# OVER_HEATING_DETECTION.net
KiCad netlist of a schematic drawn in EAGLE
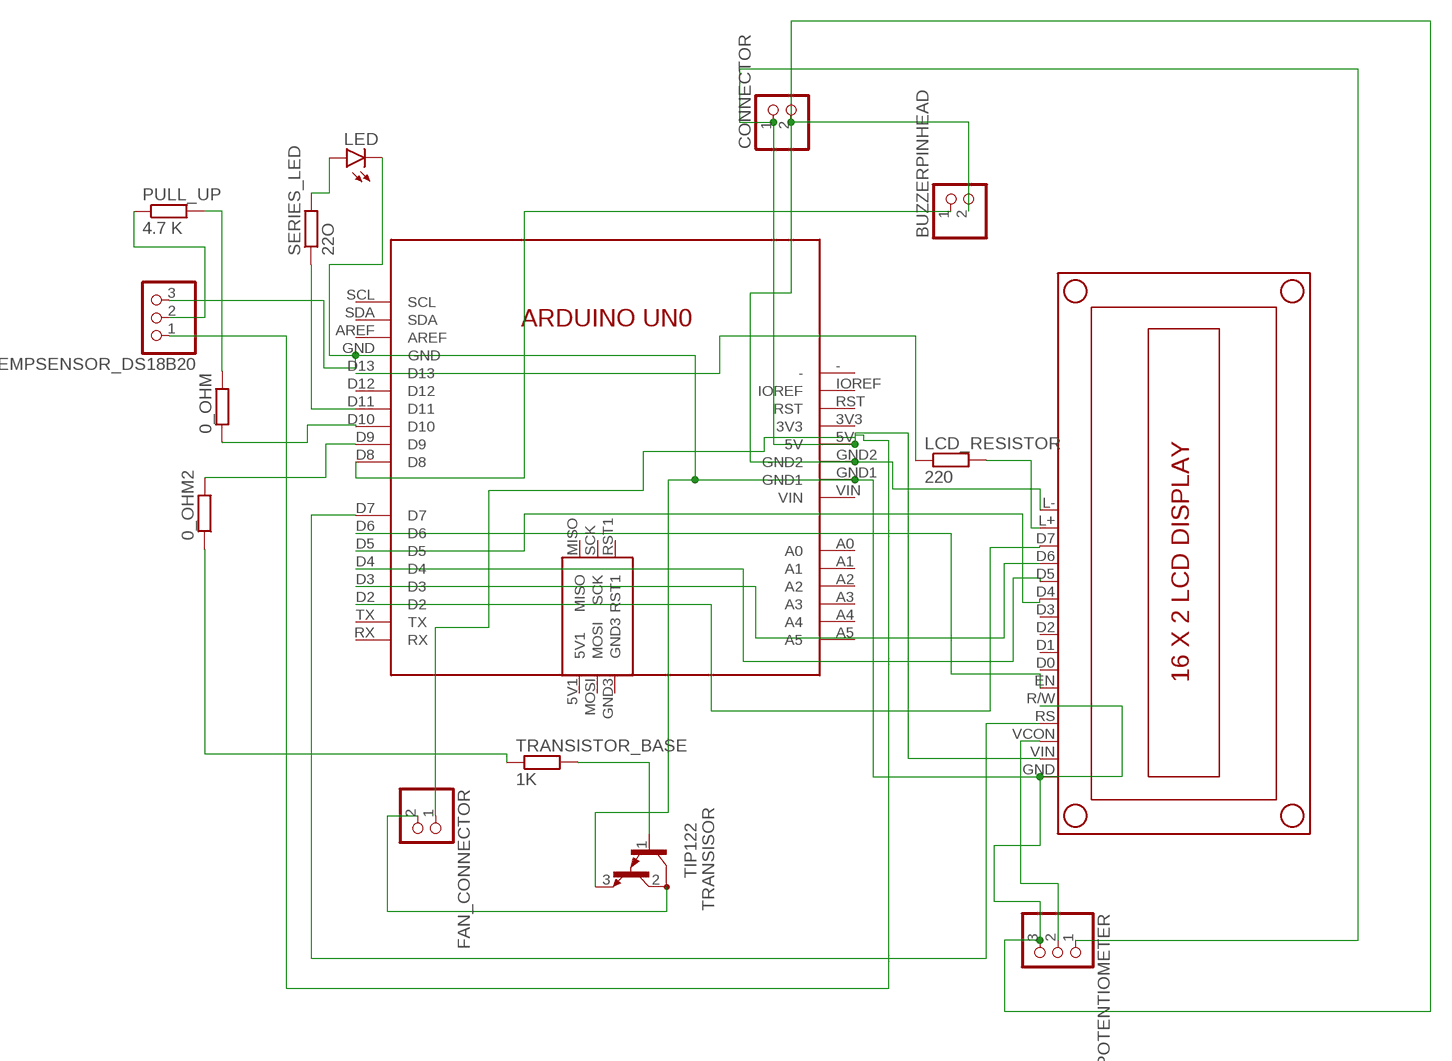
[diagram p0: schematic, sheet 1]

(export (version "E")
  (design (tool "Eeschema 10.0.6"))
  (components
    (comp (ref "0_OHM")
      (value "R-EU_0204/7")
      (footprint "eagle-import:0204_7")
      (libsource (lib "eagle-import") (part "R-EU_0204/7"))
    )
    (comp (ref "0_OHM2")
      (value "R-EU_0204/7")
      (footprint "eagle-import:0204_7")
      (libsource (lib "eagle-import") (part "R-EU_0204/7"))
    )
    (comp (ref "BUZZERPINHEAD")
      (value "PINHD-1X2")
      (footprint "eagle-import:1X02")
      (libsource (lib "eagle-import") (part "PINHD-1X2"))
    )
    (comp (ref "CONNECTOR")
      (value "PINHD-1X2")
      (footprint "eagle-import:1X02")
      (libsource (lib "eagle-import") (part "PINHD-1X2"))
    )
    (comp (ref "FAN_CONNECTOR")
      (value "PINHD-1X2")
      (footprint "eagle-import:1X02")
      (libsource (lib "eagle-import") (part "PINHD-1X2"))
    )
    (comp (ref "LCD_RESISTOR")
      (value "220")
      (footprint "eagle-import:0204_7")
      (libsource (lib "eagle-import") (part "R-EU_0204/7"))
    )
    (comp (ref "LED")
      (value "LED5MM")
      (footprint "eagle-import:LED5MM")
      (libsource (lib "eagle-import") (part "LED5MM"))
    )
    (comp (ref "POTENTIOMETER")
      (value "PINHD-1X3")
      (footprint "eagle-import:1X03")
      (libsource (lib "eagle-import") (part "PINHD-1X3"))
    )
    (comp (ref "PULL_UP")
      (value "4.7 K")
      (footprint "eagle-import:0204_7")
      (libsource (lib "eagle-import") (part "R-EU_0204/7"))
    )
    (comp (ref "SERIES_LED")
      (value "22O")
      (footprint "eagle-import:0204_7")
      (libsource (lib "eagle-import") (part "R-EU_0204/7"))
    )
    (comp (ref "TEMPSENSOR_DS18B20")
      (value "PINHD-1X3")
      (footprint "eagle-import:1X03")
      (libsource (lib "eagle-import") (part "PINHD-1X3"))
    )
    (comp (ref "TRANSISOR")
      (value "TIP122")
      (footprint "eagle-import:TO220")
      (libsource (lib "eagle-import") (part "TIP122"))
    )
    (comp (ref "TRANSISTOR_BASE")
      (value "1K")
      (footprint "eagle-import:0204_7")
      (libsource (lib "eagle-import") (part "R-EU_0204/7"))
    )
    (comp (ref "U$1")
      (value "ARDUINO_UNO")
      (footprint "eagle-import:ARDUINO_UNO")
      (libsource (lib "eagle-import") (part "ARDUINO_UNO"))
    )
    (comp (ref "U$2")
      (value "16X2_LCD_DISPLAY")
      (footprint "eagle-import:16X2_LCD_DISPLAY")
      (libsource (lib "eagle-import") (part "16X2_LCD_DISPLAY"))
    )
  )
  (nets
    (net (code "1") (name "Net-(0_OHM-Pad1)") (class "Default")
      (node (ref "0_OHM") (pin "1") (pinfunction "1_1") (pintype "passive"))
      (node (ref "U$1") (pin "D10") (pinfunction "D10_D10") (pintype "bidirectional"))
    )
    (net (code "2") (name "Net-(0_OHM-Pad2)") (class "Default")
      (node (ref "0_OHM") (pin "2") (pinfunction "2_2") (pintype "passive"))
      (node (ref "PULL_UP") (pin "2") (pinfunction "2_2") (pintype "passive"))
    )
    (net (code "3") (name "Net-(0_OHM2-Pad1)") (class "Default")
      (node (ref "0_OHM2") (pin "1") (pinfunction "1_1") (pintype "passive"))
      (node (ref "TRANSISTOR_BASE") (pin "1") (pinfunction "1_1") (pintype "passive"))
    )
    (net (code "4") (name "Net-(0_OHM2-Pad2)") (class "Default")
      (node (ref "0_OHM2") (pin "2") (pinfunction "2_2") (pintype "passive"))
      (node (ref "U$1") (pin "D9") (pinfunction "D9_D9") (pintype "bidirectional"))
    )
    (net (code "5") (name "Net-(BUZZERPINHEAD-Pad1)") (class "Default")
      (node (ref "BUZZERPINHEAD") (pin "1") (pinfunction "1_1") (pintype "passive"))
      (node (ref "U$1") (pin "D8") (pinfunction "D8_D8") (pintype "bidirectional"))
    )
    (net (code "6") (name "Net-(CONNECTOR-Pad1)") (class "Default")
      (node (ref "CONNECTOR") (pin "1") (pinfunction "1_1") (pintype "passive"))
      (node (ref "FAN_CONNECTOR") (pin "1") (pinfunction "1_1") (pintype "passive"))
      (node (ref "POTENTIOMETER") (pin "1") (pinfunction "1_1") (pintype "passive"))
      (node (ref "TEMPSENSOR_DS18B20") (pin "1") (pinfunction "1_1") (pintype "passive"))
      (node (ref "U$1") (pin "5V") (pinfunction "5V_5V") (pintype "bidirectional"))
      (node (ref "U$2") (pin "VIN") (pinfunction "VIN_VIN") (pintype "bidirectional"))
    )
    (net (code "7") (name "Net-(LCD_RESISTOR-Pad1)") (class "Default")
      (node (ref "LCD_RESISTOR") (pin "1") (pinfunction "1_1") (pintype "passive"))
      (node (ref "U$1") (pin "D13") (pinfunction "D13_D13") (pintype "bidirectional"))
    )
    (net (code "8") (name "Net-(LCD_RESISTOR-Pad2)") (class "Default")
      (node (ref "LCD_RESISTOR") (pin "2") (pinfunction "2_2") (pintype "passive"))
      (node (ref "U$2") (pin "L+") (pinfunction "L+_L+") (pintype "bidirectional"))
    )
    (net (code "9") (name "Net-(LED-C)") (class "Default")
      (node (ref "BUZZERPINHEAD") (pin "2") (pinfunction "2_2") (pintype "passive"))
      (node (ref "CONNECTOR") (pin "2") (pinfunction "2_2") (pintype "passive"))
      (node (ref "LED") (pin "K") (pinfunction "C_K") (pintype "passive"))
      (node (ref "POTENTIOMETER") (pin "3") (pinfunction "3_3") (pintype "passive"))
      (node (ref "TEMPSENSOR_DS18B20") (pin "3") (pinfunction "3_3") (pintype "passive"))
      (node (ref "TRANSISOR") (pin "3") (pinfunction "E_3") (pintype "passive"))
      (node (ref "U$1") (pin "GND") (pinfunction "GND_GND") (pintype "bidirectional"))
      (node (ref "U$1") (pin "GND1") (pinfunction "GND1_GND1") (pintype "bidirectional"))
      (node (ref "U$1") (pin "GND2") (pinfunction "GND2_GND2") (pintype "bidirectional"))
      (node (ref "U$2") (pin "GND") (pinfunction "GND_GND") (pintype "bidirectional"))
      (node (ref "U$2") (pin "L-") (pinfunction "L-_L-") (pintype "bidirectional"))
      (node (ref "U$2") (pin "R/W") (pinfunction "R/W_R/W") (pintype "bidirectional"))
    )
    (net (code "10") (name "Net-(LED-PadA)") (class "Default")
      (node (ref "LED") (pin "A") (pinfunction "A_A") (pintype "passive"))
      (node (ref "SERIES_LED") (pin "2") (pinfunction "2_2") (pintype "passive"))
    )
    (net (code "11") (name "Net-(POTENTIOMETER-Pad2)") (class "Default")
      (node (ref "POTENTIOMETER") (pin "2") (pinfunction "2_2") (pintype "passive"))
      (node (ref "U$2") (pin "VCON") (pinfunction "VCON_VCON") (pintype "bidirectional"))
    )
    (net (code "12") (name "Net-(PULL_UP-Pad1)") (class "Default")
      (node (ref "PULL_UP") (pin "1") (pinfunction "1_1") (pintype "passive"))
      (node (ref "TEMPSENSOR_DS18B20") (pin "2") (pinfunction "2_2") (pintype "passive"))
    )
    (net (code "13") (name "Net-(SERIES_LED-Pad1)") (class "Default")
      (node (ref "SERIES_LED") (pin "1") (pinfunction "1_1") (pintype "passive"))
      (node (ref "U$1") (pin "D11") (pinfunction "D11_D11") (pintype "bidirectional"))
    )
    (net (code "14") (name "Net-(TRANSISOR-B)") (class "Default")
      (node (ref "TRANSISOR") (pin "1") (pinfunction "B_1") (pintype "passive"))
      (node (ref "TRANSISTOR_BASE") (pin "2") (pinfunction "2_2") (pintype "passive"))
    )
    (net (code "15") (name "Net-(TRANSISOR-C)") (class "Default")
      (node (ref "FAN_CONNECTOR") (pin "2") (pinfunction "2_2") (pintype "passive"))
      (node (ref "TRANSISOR") (pin "2") (pinfunction "C_2") (pintype "passive"))
    )
    (net (code "16") (name "Net-(U$1-PadD2)") (class "Default")
      (node (ref "U$1") (pin "D2") (pinfunction "D2_D2") (pintype "bidirectional"))
      (node (ref "U$2") (pin "D7") (pinfunction "D7_D7") (pintype "bidirectional"))
    )
    (net (code "17") (name "Net-(U$1-PadD3)") (class "Default")
      (node (ref "U$1") (pin "D3") (pinfunction "D3_D3") (pintype "bidirectional"))
      (node (ref "U$2") (pin "D6") (pinfunction "D6_D6") (pintype "bidirectional"))
    )
    (net (code "18") (name "Net-(U$1-PadD4)") (class "Default")
      (node (ref "U$1") (pin "D4") (pinfunction "D4_D4") (pintype "bidirectional"))
      (node (ref "U$2") (pin "D5") (pinfunction "D5_D5") (pintype "bidirectional"))
    )
    (net (code "19") (name "Net-(U$1-PadD5)") (class "Default")
      (node (ref "U$1") (pin "D5") (pinfunction "D5_D5") (pintype "bidirectional"))
      (node (ref "U$2") (pin "D4") (pinfunction "D4_D4") (pintype "bidirectional"))
    )
    (net (code "20") (name "Net-(U$1-PadD6)") (class "Default")
      (node (ref "U$1") (pin "D6") (pinfunction "D6_D6") (pintype "bidirectional"))
      (node (ref "U$2") (pin "EN") (pinfunction "EN_EN") (pintype "bidirectional"))
    )
    (net (code "21") (name "Net-(U$1-PadD7)") (class "Default")
      (node (ref "U$1") (pin "D7") (pinfunction "D7_D7") (pintype "bidirectional"))
      (node (ref "U$2") (pin "RS") (pinfunction "RS_RS") (pintype "bidirectional"))
    )
    (net (code "22") (name "unconnected-(U$1-Pad-)") (class "Default")
      (node (ref "U$1") (pin "-") (pinfunction "-_-") (pintype "bidirectional"))
    )
    (net (code "23") (name "unconnected-(U$1-Pad3V3)") (class "Default")
      (node (ref "U$1") (pin "3V3") (pinfunction "3V3_3V3") (pintype "bidirectional"))
    )
    (net (code "24") (name "unconnected-(U$1-Pad5V1)") (class "Default")
      (node (ref "U$1") (pin "5V1") (pinfunction "5V1_5V1") (pintype "bidirectional"))
    )
    (net (code "25") (name "unconnected-(U$1-PadA0)") (class "Default")
      (node (ref "U$1") (pin "A0") (pinfunction "A0_A0") (pintype "bidirectional"))
    )
    (net (code "26") (name "unconnected-(U$1-PadA1)") (class "Default")
      (node (ref "U$1") (pin "A1") (pinfunction "A1_A1") (pintype "bidirectional"))
    )
    (net (code "27") (name "unconnected-(U$1-PadA2)") (class "Default")
      (node (ref "U$1") (pin "A2") (pinfunction "A2_A2") (pintype "bidirectional"))
    )
    (net (code "28") (name "unconnected-(U$1-PadA3)") (class "Default")
      (node (ref "U$1") (pin "A3") (pinfunction "A3_A3") (pintype "bidirectional"))
    )
    (net (code "29") (name "unconnected-(U$1-PadA4)") (class "Default")
      (node (ref "U$1") (pin "A4") (pinfunction "A4_A4") (pintype "bidirectional"))
    )
    (net (code "30") (name "unconnected-(U$1-PadA5)") (class "Default")
      (node (ref "U$1") (pin "A5") (pinfunction "A5_A5") (pintype "bidirectional"))
    )
    (net (code "31") (name "unconnected-(U$1-PadAREF)") (class "Default")
      (node (ref "U$1") (pin "AREF") (pinfunction "AREF_AREF") (pintype "bidirectional"))
    )
    (net (code "32") (name "unconnected-(U$1-PadD12)") (class "Default")
      (node (ref "U$1") (pin "D12") (pinfunction "D12_D12") (pintype "bidirectional"))
    )
    (net (code "33") (name "unconnected-(U$1-PadGND3)") (class "Default")
      (node (ref "U$1") (pin "GND3") (pinfunction "GND3_GND3") (pintype "bidirectional"))
    )
    (net (code "34") (name "unconnected-(U$1-PadIOREF)") (class "Default")
      (node (ref "U$1") (pin "IOREF") (pinfunction "IOREF_IOREF") (pintype "bidirectional"))
    )
    (net (code "35") (name "unconnected-(U$1-PadMISO)") (class "Default")
      (node (ref "U$1") (pin "MISO") (pinfunction "MISO_MISO") (pintype "bidirectional"))
    )
    (net (code "36") (name "unconnected-(U$1-PadMOSI)") (class "Default")
      (node (ref "U$1") (pin "MOSI") (pinfunction "MOSI_MOSI") (pintype "bidirectional"))
    )
    (net (code "37") (name "unconnected-(U$1-PadRST)") (class "Default")
      (node (ref "U$1") (pin "RST") (pinfunction "RST_RST") (pintype "bidirectional"))
    )
    (net (code "38") (name "unconnected-(U$1-PadRST1)") (class "Default")
      (node (ref "U$1") (pin "RST1") (pinfunction "RST1_RST1") (pintype "bidirectional"))
    )
    (net (code "39") (name "unconnected-(U$1-PadRX)") (class "Default")
      (node (ref "U$1") (pin "RX") (pinfunction "RX_RX") (pintype "bidirectional"))
    )
    (net (code "40") (name "unconnected-(U$1-PadSCK)") (class "Default")
      (node (ref "U$1") (pin "SCK") (pinfunction "SCK_SCK") (pintype "bidirectional"))
    )
    (net (code "41") (name "unconnected-(U$1-PadSCL)") (class "Default")
      (node (ref "U$1") (pin "SCL") (pinfunction "SCL_SCL") (pintype "bidirectional"))
    )
    (net (code "42") (name "unconnected-(U$1-PadSDA)") (class "Default")
      (node (ref "U$1") (pin "SDA") (pinfunction "SDA_SDA") (pintype "bidirectional"))
    )
    (net (code "43") (name "unconnected-(U$1-PadTX)") (class "Default")
      (node (ref "U$1") (pin "TX") (pinfunction "TX_TX") (pintype "bidirectional"))
    )
    (net (code "44") (name "unconnected-(U$1-PadVIN)") (class "Default")
      (node (ref "U$1") (pin "VIN") (pinfunction "VIN_VIN") (pintype "bidirectional"))
    )
    (net (code "45") (name "unconnected-(U$2-PadD0)") (class "Default")
      (node (ref "U$2") (pin "D0") (pinfunction "D0_D0") (pintype "bidirectional"))
    )
    (net (code "46") (name "unconnected-(U$2-PadD1)") (class "Default")
      (node (ref "U$2") (pin "D1") (pinfunction "D1_D1") (pintype "bidirectional"))
    )
    (net (code "47") (name "unconnected-(U$2-PadD2)") (class "Default")
      (node (ref "U$2") (pin "D2") (pinfunction "D2_D2") (pintype "bidirectional"))
    )
    (net (code "48") (name "unconnected-(U$2-PadD3)") (class "Default")
      (node (ref "U$2") (pin "D3") (pinfunction "D3_D3") (pintype "bidirectional"))
    )
  )
)
